# PowerConverter.net
KiCad netlist of a schematic drawn in Altium Designer
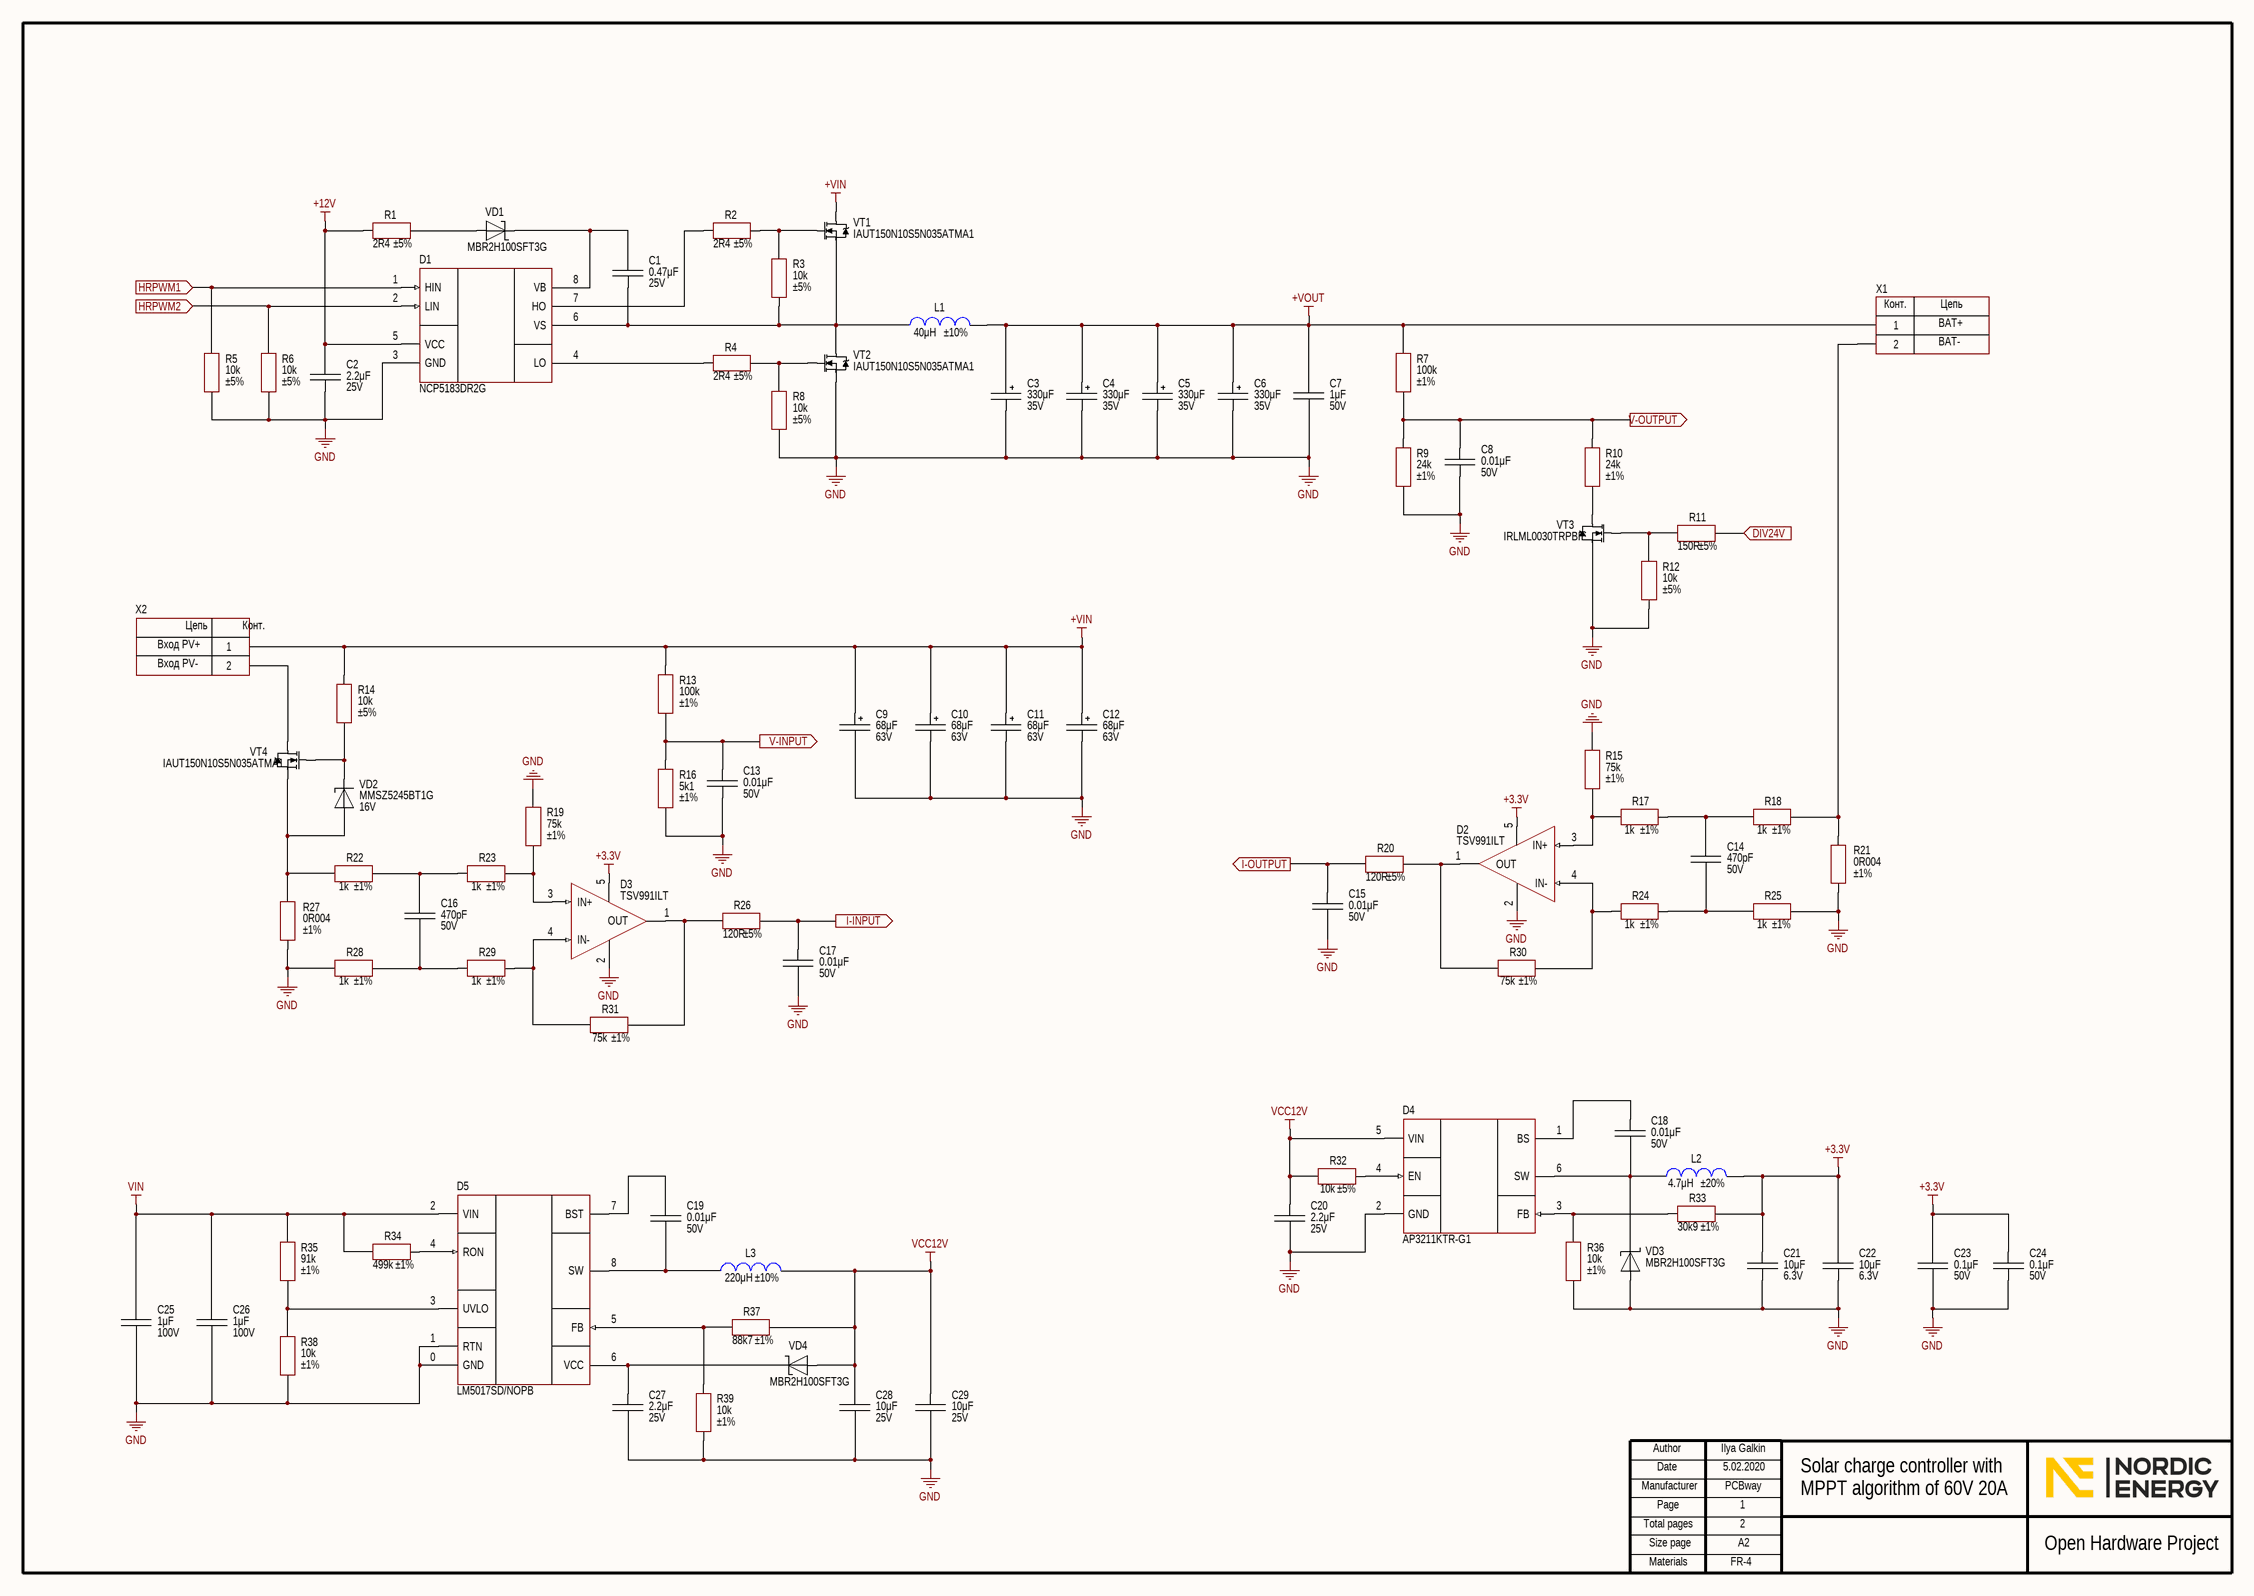
[diagram p0: PowerConverter.SchDoc]

(export (version "E")
  (design (tool "Eeschema 10.0.6"))
  (components
    (comp (ref "C1")
      (value "0.47μF")
      (footprint "CAP: 0805")
      (fields
        (field (name "MANUFACTURER") "Samsung")
        (field (name "PARTNUMBER") "CL21B474KAFNNNG")
        (field (name "VALUEMANUFACTURERPARTNUMBER") "Ceramic capacitor, 0.47μF, X7R, ±10%, 25V, 0805, -55...+125°C")
        (field (name "VOLTAGE") "25V")
      )
      (libsource (lib "Capacitor") (part "Ceramic_0805"))
    )
    (comp (ref "C2")
      (value "2.2μF")
      (footprint "CAP: 0805")
      (fields
        (field (name "MANUFACTURER") "Samsung")
        (field (name "PARTNUMBER") "CL21B225KAFNFNE")
        (field (name "VALUEMANUFACTURERPARTNUMBER") "Ceramic capacitor, 2.2μF, X7R, ±10%, 25V, 0805, -55...+125°C")
        (field (name "VOLTAGE") "25V")
      )
      (libsource (lib "Capacitor") (part "Ceramic_0805"))
    )
    (comp (ref "C3")
      (value "330μF")
      (footprint "CAP: D10C5H12.5")
      (fields
        (field (name "MANUFACTURER") "Panasonic")
        (field (name "PARTNUMBER") "35SEK330M")
        (field (name "VALUEMANUFACTURERPARTNUMBER") "Solid polymer capacitor, 330μF, 35V, ±20%, 18mOhm, 13x10x5 mm, -55...+105°C")
        (field (name "VOLTAGE") "35V")
      )
      (libsource (lib "Capacitor") (part "Aluminium"))
    )
    (comp (ref "C4")
      (value "330μF")
      (footprint "CAP: D10C5H12.5")
      (fields
        (field (name "MANUFACTURER") "Panasonic")
        (field (name "PARTNUMBER") "35SEK330M")
        (field (name "VALUEMANUFACTURERPARTNUMBER") "Solid polymer capacitor, 330μF, 35V, ±20%, 18mOhm, 13x10x5 mm, -55...+105°C")
        (field (name "VOLTAGE") "35V")
      )
      (libsource (lib "Capacitor") (part "Aluminium"))
    )
    (comp (ref "C5")
      (value "330μF")
      (footprint "CAP: D10C5H12.5")
      (fields
        (field (name "MANUFACTURER") "Panasonic")
        (field (name "PARTNUMBER") "35SEK330M")
        (field (name "VALUEMANUFACTURERPARTNUMBER") "Solid polymer capacitor, 330μF, 35V, ±20%, 18mOhm, 13x10x5 mm, -55...+105°C")
        (field (name "VOLTAGE") "35V")
      )
      (libsource (lib "Capacitor") (part "Aluminium"))
    )
    (comp (ref "C6")
      (value "330μF")
      (footprint "CAP: D10C5H12.5")
      (fields
        (field (name "MANUFACTURER") "Panasonic")
        (field (name "PARTNUMBER") "35SEK330M")
        (field (name "VALUEMANUFACTURERPARTNUMBER") "Solid polymer capacitor, 330μF, 35V, ±20%, 18mOhm, 13x10x5 mm, -55...+105°C")
        (field (name "VOLTAGE") "35V")
      )
      (libsource (lib "Capacitor") (part "Aluminium"))
    )
    (comp (ref "C7")
      (value "1μF")
      (footprint "CAP: 0805")
      (fields
        (field (name "MANUFACTURER") "Samsung")
        (field (name "PARTNUMBER") "CL21B105KBFNNNG")
        (field (name "VALUEMANUFACTURERPARTNUMBER") "Ceramic capacitor, 1μF, X7R, ±10%, 50V, 0805, -55...+125°C")
        (field (name "VOLTAGE") "50V")
      )
      (libsource (lib "Capacitor") (part "Ceramic_0805"))
    )
    (comp (ref "C8")
      (value "0.01μF")
      (footprint "CAP: 0805")
      (fields
        (field (name "MANUFACTURER") "Samsung")
        (field (name "PARTNUMBER") "CL21B103KBANNNC")
        (field (name "VALUEMANUFACTURERPARTNUMBER") "Ceramic capacitor, 0.01μF, X7R, ±10%, 50V, 0805, -55...+125°C")
        (field (name "VOLTAGE") "50V")
      )
      (libsource (lib "Capacitor") (part "Ceramic_0805"))
    )
    (comp (ref "C9")
      (value "68μF")
      (footprint "CAP: D10C5H12.5")
      (fields
        (field (name "MANUFACTURER") "Panasonic")
        (field (name "PARTNUMBER") "63SXE68M")
        (field (name "VALUEMANUFACTURERPARTNUMBER") "Solid polymer capacitor, 68μF, 63V, ±20%, 25mOhm, 13x10x5 mm, -55...+105°C")
        (field (name "VOLTAGE") "63V")
      )
      (libsource (lib "Capacitor") (part "Aluminium"))
    )
    (comp (ref "C10")
      (value "68μF")
      (footprint "CAP: D10C5H12.5")
      (fields
        (field (name "MANUFACTURER") "Panasonic")
        (field (name "PARTNUMBER") "63SXE68M")
        (field (name "VALUEMANUFACTURERPARTNUMBER") "Solid polymer capacitor, 68μF, 63V, ±20%, 25mOhm, 13x10x5 mm, -55...+105°C")
        (field (name "VOLTAGE") "63V")
      )
      (libsource (lib "Capacitor") (part "Aluminium"))
    )
    (comp (ref "C11")
      (value "68μF")
      (footprint "CAP: D10C5H12.5")
      (fields
        (field (name "MANUFACTURER") "Panasonic")
        (field (name "PARTNUMBER") "63SXE68M")
        (field (name "VALUEMANUFACTURERPARTNUMBER") "Solid polymer capacitor, 68μF, 63V, ±20%, 25mOhm, 13x10x5 mm, -55...+105°C")
        (field (name "VOLTAGE") "63V")
      )
      (libsource (lib "Capacitor") (part "Aluminium"))
    )
    (comp (ref "C12")
      (value "68μF")
      (footprint "CAP: D10C5H12.5")
      (fields
        (field (name "MANUFACTURER") "Panasonic")
        (field (name "PARTNUMBER") "63SXE68M")
        (field (name "VALUEMANUFACTURERPARTNUMBER") "Solid polymer capacitor, 68μF, 63V, ±20%, 25mOhm, 13x10x5 mm, -55...+105°C")
        (field (name "VOLTAGE") "63V")
      )
      (libsource (lib "Capacitor") (part "Aluminium"))
    )
    (comp (ref "C13")
      (value "0.01μF")
      (footprint "CAP: 0805")
      (fields
        (field (name "MANUFACTURER") "Samsung")
        (field (name "PARTNUMBER") "CL21B103KBANNNC")
        (field (name "VALUEMANUFACTURERPARTNUMBER") "Ceramic capacitor, 0.01μF, X7R, ±10%, 50V, 0805, -55...+125°C")
        (field (name "VOLTAGE") "50V")
      )
      (libsource (lib "Capacitor") (part "Ceramic_0805"))
    )
    (comp (ref "C14")
      (value "470pF")
      (footprint "CAP: 0805")
      (fields
        (field (name "MANUFACTURER") "Samsung")
        (field (name "PARTNUMBER") "CL21B471KBANNNC")
        (field (name "VALUEMANUFACTURERPARTNUMBER") "Ceramic capacitor, 470pF, X7R, ±10%, 50V, 0805, -55...+125°C")
        (field (name "VOLTAGE") "50V")
      )
      (libsource (lib "Capacitor") (part "Ceramic_0805"))
    )
    (comp (ref "C15")
      (value "0.01μF")
      (footprint "CAP: 0805")
      (fields
        (field (name "MANUFACTURER") "Samsung")
        (field (name "PARTNUMBER") "CL21B103KBANNNC")
        (field (name "VALUEMANUFACTURERPARTNUMBER") "Ceramic capacitor, 0.01μF, X7R, ±10%, 50V, 0805, -55...+125°C")
        (field (name "VOLTAGE") "50V")
      )
      (libsource (lib "Capacitor") (part "Ceramic_0805"))
    )
    (comp (ref "C16")
      (value "470pF")
      (footprint "CAP: 0805")
      (fields
        (field (name "MANUFACTURER") "Samsung")
        (field (name "PARTNUMBER") "CL21B471KBANNNC")
        (field (name "VALUEMANUFACTURERPARTNUMBER") "Ceramic capacitor, 470pF, X7R, ±10%, 50V, 0805, -55...+125°C")
        (field (name "VOLTAGE") "50V")
      )
      (libsource (lib "Capacitor") (part "Ceramic_0805"))
    )
    (comp (ref "C17")
      (value "0.01μF")
      (footprint "CAP: 0805")
      (fields
        (field (name "MANUFACTURER") "Samsung")
        (field (name "PARTNUMBER") "CL21B103KBANNNC")
        (field (name "VALUEMANUFACTURERPARTNUMBER") "Ceramic capacitor, 0.01μF, X7R, ±10%, 50V, 0805, -55...+125°C")
        (field (name "VOLTAGE") "50V")
      )
      (libsource (lib "Capacitor") (part "Ceramic_0805"))
    )
    (comp (ref "C18")
      (value "0.01μF")
      (footprint "CAP: 0805")
      (fields
        (field (name "MANUFACTURER") "Samsung")
        (field (name "PARTNUMBER") "CL21B103KBANNNC")
        (field (name "VALUEMANUFACTURERPARTNUMBER") "Ceramic capacitor, 0.01μF, X7R, ±10%, 50V, 0805, -55...+125°C")
        (field (name "VOLTAGE") "50V")
      )
      (libsource (lib "Capacitor") (part "Ceramic_0805"))
    )
    (comp (ref "C19")
      (value "0.01μF")
      (footprint "CAP: 0805")
      (fields
        (field (name "MANUFACTURER") "Samsung")
        (field (name "PARTNUMBER") "CL21B103KBANNNC")
        (field (name "VALUEMANUFACTURERPARTNUMBER") "Ceramic capacitor, 0.01μF, X7R, ±10%, 50V, 0805, -55...+125°C")
        (field (name "VOLTAGE") "50V")
      )
      (libsource (lib "Capacitor") (part "Ceramic_0805"))
    )
    (comp (ref "C20")
      (value "2.2μF")
      (footprint "CAP: 0805")
      (fields
        (field (name "MANUFACTURER") "Samsung")
        (field (name "PARTNUMBER") "CL21B225KAFNFNE")
        (field (name "VALUEMANUFACTURERPARTNUMBER") "Ceramic capacitor, 2.2μF, X7R, ±10%, 25V, 0805, -55...+125°C")
        (field (name "VOLTAGE") "25V")
      )
      (libsource (lib "Capacitor") (part "Ceramic_0805"))
    )
    (comp (ref "C21")
      (value "10μF")
      (footprint "CAP: 0805")
      (fields
        (field (name "MANUFACTURER") "Samsung")
        (field (name "PARTNUMBER") "CL21B106KQQNNNG")
        (field (name "VALUEMANUFACTURERPARTNUMBER") "Ceramic capacitor, 10μF, X7R, ±10%, 6.3V, 0805, -55...+125°C")
        (field (name "VOLTAGE") "6.3V")
      )
      (libsource (lib "Capacitor") (part "Ceramic_0805"))
    )
    (comp (ref "C22")
      (value "10μF")
      (footprint "CAP: 0805")
      (fields
        (field (name "MANUFACTURER") "Samsung")
        (field (name "PARTNUMBER") "CL21B106KQQNNNG")
        (field (name "VALUEMANUFACTURERPARTNUMBER") "Ceramic capacitor, 10μF, X7R, ±10%, 6.3V, 0805, -55...+125°C")
        (field (name "VOLTAGE") "6.3V")
      )
      (libsource (lib "Capacitor") (part "Ceramic_0805"))
    )
    (comp (ref "C23")
      (value "0.1μF")
      (footprint "CAP: 0805")
      (fields
        (field (name "MANUFACTURER") "Samsung")
        (field (name "PARTNUMBER") "CL21B104KBCNFNC")
        (field (name "VALUEMANUFACTURERPARTNUMBER") "Ceramic capacitor, 0.1μF, X7R, ±10%, 50V, 0805, -55...+125°C")
        (field (name "VOLTAGE") "50V")
      )
      (libsource (lib "Capacitor") (part "Ceramic_0805"))
    )
    (comp (ref "C24")
      (value "0.1μF")
      (footprint "CAP: 0805")
      (fields
        (field (name "MANUFACTURER") "Samsung")
        (field (name "PARTNUMBER") "CL21B104KBCNFNC")
        (field (name "VALUEMANUFACTURERPARTNUMBER") "Ceramic capacitor, 0.1μF, X7R, ±10%, 50V, 0805, -55...+125°C")
        (field (name "VOLTAGE") "50V")
      )
      (libsource (lib "Capacitor") (part "Ceramic_0805"))
    )
    (comp (ref "C25")
      (value "1μF")
      (footprint "CAP: 1206")
      (fields
        (field (name "MANUFACTURER") "Samsung")
        (field (name "PARTNUMBER") "CL31B105KCHSNNE")
        (field (name "VALUEMANUFACTURERPARTNUMBER") "Ceramic capacitor, 1μF, X7R, ±10%, 100V, 1206, -55...+125°C")
        (field (name "VOLTAGE") "100V")
      )
      (libsource (lib "Capacitor") (part "Ceramic_1206"))
    )
    (comp (ref "C26")
      (value "1μF")
      (footprint "CAP: 1206")
      (fields
        (field (name "MANUFACTURER") "Samsung")
        (field (name "PARTNUMBER") "CL31B105KCHSNNE")
        (field (name "VALUEMANUFACTURERPARTNUMBER") "Ceramic capacitor, 1μF, X7R, ±10%, 100V, 1206, -55...+125°C")
        (field (name "VOLTAGE") "100V")
      )
      (libsource (lib "Capacitor") (part "Ceramic_1206"))
    )
    (comp (ref "C27")
      (value "2.2μF")
      (footprint "CAP: 0805")
      (fields
        (field (name "MANUFACTURER") "Samsung")
        (field (name "PARTNUMBER") "CL21B225KAFNFNE")
        (field (name "VALUEMANUFACTURERPARTNUMBER") "Ceramic capacitor, 2.2μF, X7R, ±10%, 25V, 0805, -55...+125°C")
        (field (name "VOLTAGE") "25V")
      )
      (libsource (lib "Capacitor") (part "Ceramic_0805"))
    )
    (comp (ref "C28")
      (value "10μF")
      (footprint "CAP: 1206")
      (fields
        (field (name "MANUFACTURER") "Samsung")
        (field (name "PARTNUMBER") "CL31B106KAHNNNE")
        (field (name "VALUEMANUFACTURERPARTNUMBER") "Ceramic capacitor, 10μF, X7R, ±10%, 25V, 1206, -55...+125°C")
        (field (name "VOLTAGE") "25V")
      )
      (libsource (lib "Capacitor") (part "Ceramic_1206"))
    )
    (comp (ref "C29")
      (value "10μF")
      (footprint "CAP: 1206")
      (fields
        (field (name "MANUFACTURER") "Samsung")
        (field (name "PARTNUMBER") "CL31B106KAHNNNE")
        (field (name "VALUEMANUFACTURERPARTNUMBER") "Ceramic capacitor, 10μF, X7R, ±10%, 25V, 1206, -55...+125°C")
        (field (name "VOLTAGE") "25V")
      )
      (libsource (lib "Capacitor") (part "Ceramic_1206"))
    )
    (comp (ref "D1")
      (value "~")
      (footprint "8-SOIC")
      (description "Gate driver")
      (fields
        (field (name "MANUFACTURER") "ON Semiconductor")
        (field (name "VALUEMANUFACTURERPARTNUMBER") "Half-bridge gate driver, 600V, 500kHz, ±4.3A, supply 9...18V, -40...+125°C, 8-SOIC")
        (field (name "PARTNUMBER") "NCP5183DR2G")
      )
      (libsource (lib "IC. Gate driver") (part "NCP5183DR2G"))
    )
    (comp (ref "D2")
      (value "~")
      (footprint "SOT23-5")
      (description "OP amplifier")
      (fields
        (field (name "MANUFACTURER") "STMicroelectronics")
        (field (name "VALUEMANUFACTURERPARTNUMBER") "IC op amplifier, Rail-to-Rail, 20 MHz, 2.7...5.5V, -40...+125°C, SOT23-5")
        (field (name "PARTNUMBER") "TSV991ILT")
      )
      (libsource (lib "IC. Amplifier") (part "TSV991ILT"))
    )
    (comp (ref "D3")
      (value "~")
      (footprint "SOT23-5")
      (description "OP amplifier")
      (fields
        (field (name "MANUFACTURER") "STMicroelectronics")
        (field (name "VALUEMANUFACTURERPARTNUMBER") "IC op amplifier, Rail-to-Rail, 20 MHz, 2.7...5.5V, -40...+125°C, SOT23-5")
        (field (name "PARTNUMBER") "TSV991ILT")
      )
      (libsource (lib "IC. Amplifier") (part "TSV991ILT"))
    )
    (comp (ref "D4")
      (value "~")
      (footprint "SOT23-6")
      (description "Buck converter")
      (fields
        (field (name "MANUFACTURER") "Diodes Incorporated")
        (field (name "VALUEMANUFACTURERPARTNUMBER") "DC/DC buck converter, input 4.5...18V, 1.4MHz, output 0.81...15V, 1.5A, -40...+85°C, SOT23-6")
        (field (name "PARTNUMBER") "AP3211KTR-G1")
      )
      (libsource (lib "IC. Power supply") (part "AP3211KTR-G1"))
    )
    (comp (ref "D5")
      (value "~")
      (footprint "8-WSON (4x4)")
      (description "Buck converter")
      (fields
        (field (name "MANUFACTURER") "Texas Instruments")
        (field (name "VALUEMANUFACTURERPARTNUMBER") "DC/DC buck converter, input 7.5...100V, 1MHz, output 1.225...90V, 0.6A, -40...+125°C, 8-WSON")
        (field (name "PARTNUMBER") "LM5017SD/NOPB")
      )
      (libsource (lib "IC. Power supply") (part "LM5017SD"))
    )
    (comp (ref "L1")
      (value "40μH")
      (footprint "IND: R32.8/20.1/10.7 (L)")
      (fields
        (field (name "MANUFACTURER") "Magnetics")
        (field (name "PARTNUMBER") "0077548A7")
        (field (name "VALUEMANUFACTURERPARTNUMBER") "Fixed inductor, 40μH, ±10%, R32.8/20.1/10.7, Kool Mu, µ=125, 127 нГн/витков2")
        (field (name "TOLERANCE") "±10%")
      )
      (libsource (lib "Inductor") (part "Inductor_R32.8/20.1/10.7"))
    )
    (comp (ref "L2")
      (value "4.7μH")
      (footprint "IND: SDR0403")
      (fields
        (field (name "MANUFACTURER") "Bourns")
        (field (name "PARTNUMBER") "SDR0403-4R7ML")
        (field (name "VALUEMANUFACTURERPARTNUMBER") "Fixed inductor, 4.7μH, ±20%, SDR0403, 1.7A, -40...+125°C")
        (field (name "TOLERANCE") "±20%")
      )
      (libsource (lib "Inductor") (part "Inductor_SDR0403"))
    )
    (comp (ref "L3")
      (value "220μH")
      (footprint "IND: SDR0805")
      (fields
        (field (name "MANUFACTURER") "Bourns")
        (field (name "PARTNUMBER") "SDR0805-221KL")
        (field (name "VALUEMANUFACTURERPARTNUMBER") "Fixed inductor, 220μH, ±10%, SDR0805, 490mA, -40...+125°C")
        (field (name "TOLERANCE") "±10%")
      )
      (libsource (lib "Inductor") (part "Inductor_SDR0805"))
    )
    (comp (ref "R1")
      (value "2R4")
      (footprint "RES: 0805")
      (fields
        (field (name "MANUFACTURER") "Yageo")
        (field (name "PARTNUMBER") "RC0805JR-072R4L")
        (field (name "VALUEMANUFACTURERPARTNUMBER") "Resistor film, 2R4, ±5%, 0805, 0.125W, -55...+125°C")
        (field (name "TOLERANCE") "±5%")
      )
      (libsource (lib "Resistor") (part "Resistor_0805"))
    )
    (comp (ref "R2")
      (value "2R4")
      (footprint "RES: 0805")
      (fields
        (field (name "MANUFACTURER") "Yageo")
        (field (name "PARTNUMBER") "RC0805JR-072R4L")
        (field (name "VALUEMANUFACTURERPARTNUMBER") "Resistor film, 2R4, ±5%, 0805, 0.125W, -55...+125°C")
        (field (name "TOLERANCE") "±5%")
      )
      (libsource (lib "Resistor") (part "Resistor_0805"))
    )
    (comp (ref "R3")
      (value "10k")
      (footprint "RES: 0805")
      (fields
        (field (name "MANUFACTURER") "Yageo")
        (field (name "PARTNUMBER") "RC0805JR-0710KL")
        (field (name "VALUEMANUFACTURERPARTNUMBER") "Resistor film, 10k, ±5%, 0805, 0.125W, -55...+125°C")
        (field (name "TOLERANCE") "±5%")
      )
      (libsource (lib "") (part "Resistor_0805_1"))
    )
    (comp (ref "R4")
      (value "2R4")
      (footprint "RES: 0805")
      (fields
        (field (name "MANUFACTURER") "Yageo")
        (field (name "PARTNUMBER") "RC0805JR-072R4L")
        (field (name "VALUEMANUFACTURERPARTNUMBER") "Resistor film, 2R4, ±5%, 0805, 0.125W, -55...+125°C")
        (field (name "TOLERANCE") "±5%")
      )
      (libsource (lib "Resistor") (part "Resistor_0805"))
    )
    (comp (ref "R5")
      (value "10k")
      (footprint "RES: 0805")
      (fields
        (field (name "MANUFACTURER") "Yageo")
        (field (name "PARTNUMBER") "RC0805JR-0710KL")
        (field (name "VALUEMANUFACTURERPARTNUMBER") "Resistor film, 10k, ±5%, 0805, 0.125W, -55...+125°C")
        (field (name "TOLERANCE") "±5%")
      )
      (libsource (lib "") (part "Resistor_0805_1"))
    )
    (comp (ref "R6")
      (value "10k")
      (footprint "RES: 0805")
      (fields
        (field (name "MANUFACTURER") "Yageo")
        (field (name "PARTNUMBER") "RC0805JR-0710KL")
        (field (name "VALUEMANUFACTURERPARTNUMBER") "Resistor film, 10k, ±5%, 0805, 0.125W, -55...+125°C")
        (field (name "TOLERANCE") "±5%")
      )
      (libsource (lib "") (part "Resistor_0805_1"))
    )
    (comp (ref "R7")
      (value "100k")
      (footprint "RES: 0805")
      (fields
        (field (name "MANUFACTURER") "Yageo")
        (field (name "PARTNUMBER") "RC0805FR-07100KL")
        (field (name "VALUEMANUFACTURERPARTNUMBER") "Resistor film, 100k, ±1%, 0805, 0.125W, -55...+125°C")
        (field (name "TOLERANCE") "±1%")
      )
      (libsource (lib "") (part "Resistor_0805_1"))
    )
    (comp (ref "R8")
      (value "10k")
      (footprint "RES: 0805")
      (fields
        (field (name "MANUFACTURER") "Yageo")
        (field (name "PARTNUMBER") "RC0805JR-0710KL")
        (field (name "VALUEMANUFACTURERPARTNUMBER") "Resistor film, 10k, ±5%, 0805, 0.125W, -55...+125°C")
        (field (name "TOLERANCE") "±5%")
      )
      (libsource (lib "") (part "Resistor_0805_1"))
    )
    (comp (ref "R9")
      (value "24k")
      (footprint "RES: 0805")
      (fields
        (field (name "MANUFACTURER") "Yageo")
        (field (name "PARTNUMBER") "RC0805FR-0724KL")
        (field (name "VALUEMANUFACTURERPARTNUMBER") "Resistor film, 24k, ±1%, 0805, 0.125W, -55...+125°C")
        (field (name "TOLERANCE") "±1%")
      )
      (libsource (lib "") (part "Resistor_0805_1"))
    )
    (comp (ref "R10")
      (value "24k")
      (footprint "RES: 0805")
      (fields
        (field (name "MANUFACTURER") "Yageo")
        (field (name "PARTNUMBER") "RC0805FR-0724KL")
        (field (name "VALUEMANUFACTURERPARTNUMBER") "Resistor film, 24k, ±1%, 0805, 0.125W, -55...+125°C")
        (field (name "TOLERANCE") "±1%")
      )
      (libsource (lib "") (part "Resistor_0805_1"))
    )
    (comp (ref "R11")
      (value "150R")
      (footprint "RES: 0805")
      (fields
        (field (name "MANUFACTURER") "Yageo")
        (field (name "PARTNUMBER") "RC0805JR-07150RL")
        (field (name "VALUEMANUFACTURERPARTNUMBER") "Resistor film, 150R, ±5%, 0805, 0.125W, -55...+125°C")
        (field (name "TOLERANCE") "±5%")
      )
      (libsource (lib "Resistor") (part "Resistor_0805"))
    )
    (comp (ref "R12")
      (value "10k")
      (footprint "RES: 0805")
      (fields
        (field (name "MANUFACTURER") "Yageo")
        (field (name "PARTNUMBER") "RC0805JR-0710KL")
        (field (name "VALUEMANUFACTURERPARTNUMBER") "Resistor film, 10k, ±5%, 0805, 0.125W, -55...+125°C")
        (field (name "TOLERANCE") "±5%")
      )
      (libsource (lib "") (part "Resistor_0805_1"))
    )
    (comp (ref "R13")
      (value "100k")
      (footprint "RES: 0805")
      (fields
        (field (name "MANUFACTURER") "Yageo")
        (field (name "PARTNUMBER") "RC0805FR-07100KL")
        (field (name "VALUEMANUFACTURERPARTNUMBER") "Resistor film, 100k, ±1%, 0805, 0.125W, -55...+125°C")
        (field (name "TOLERANCE") "±1%")
      )
      (libsource (lib "") (part "Resistor_0805_1"))
    )
    (comp (ref "R14")
      (value "10k")
      (footprint "RES: 0805")
      (fields
        (field (name "MANUFACTURER") "Yageo")
        (field (name "PARTNUMBER") "RC0805JR-0710KL")
        (field (name "VALUEMANUFACTURERPARTNUMBER") "Resistor film, 10k, ±5%, 0805, 0.125W, -55...+125°C")
        (field (name "TOLERANCE") "±5%")
      )
      (libsource (lib "") (part "Resistor_0805_1"))
    )
    (comp (ref "R15")
      (value "75k")
      (footprint "RES: 0805")
      (fields
        (field (name "MANUFACTURER") "Yageo")
        (field (name "PARTNUMBER") "RC0805FR-0775KL")
        (field (name "VALUEMANUFACTURERPARTNUMBER") "Resistor film, 75k, ±1%, 0805, 0.125W, -55...+125°C")
        (field (name "TOLERANCE") "±1%")
      )
      (libsource (lib "") (part "Resistor_0805_1"))
    )
    (comp (ref "R16")
      (value "5k1")
      (footprint "RES: 0805")
      (fields
        (field (name "MANUFACTURER") "Yageo")
        (field (name "PARTNUMBER") "RC0805FR-075K1L")
        (field (name "VALUEMANUFACTURERPARTNUMBER") "Resistor film, 5k1, ±1%, 0805, 0.125W, -55...+125°C")
        (field (name "TOLERANCE") "±1%")
      )
      (libsource (lib "") (part "Resistor_0805_1"))
    )
    (comp (ref "R17")
      (value "1k")
      (footprint "RES: 0805")
      (fields
        (field (name "MANUFACTURER") "Yageo")
        (field (name "PARTNUMBER") "RC0805FR-071KL")
        (field (name "VALUEMANUFACTURERPARTNUMBER") "Resistor film, 1k, ±1%, 0805, 0.125W, -55...+125°C")
        (field (name "TOLERANCE") "±1%")
      )
      (libsource (lib "Resistor") (part "Resistor_0805"))
    )
    (comp (ref "R18")
      (value "1k")
      (footprint "RES: 0805")
      (fields
        (field (name "MANUFACTURER") "Yageo")
        (field (name "PARTNUMBER") "RC0805FR-071KL")
        (field (name "VALUEMANUFACTURERPARTNUMBER") "Resistor film, 1k, ±1%, 0805, 0.125W, -55...+125°C")
        (field (name "TOLERANCE") "±1%")
      )
      (libsource (lib "Resistor") (part "Resistor_0805"))
    )
    (comp (ref "R19")
      (value "75k")
      (footprint "RES: 0805")
      (fields
        (field (name "MANUFACTURER") "Yageo")
        (field (name "PARTNUMBER") "RC0805FR-0775KL")
        (field (name "VALUEMANUFACTURERPARTNUMBER") "Resistor film, 75k, ±1%, 0805, 0.125W, -55...+125°C")
        (field (name "TOLERANCE") "±1%")
      )
      (libsource (lib "") (part "Resistor_0805_1"))
    )
    (comp (ref "R20")
      (value "120R")
      (footprint "RES: 0805")
      (fields
        (field (name "MANUFACTURER") "Yageo")
        (field (name "PARTNUMBER") "RC0805JR-07120RL")
        (field (name "VALUEMANUFACTURERPARTNUMBER") "Resistor film, 120R, ±5%, 0805, 0.125W, -55...+125°C")
        (field (name "TOLERANCE") "±5%")
      )
      (libsource (lib "Resistor") (part "Resistor_0805"))
    )
    (comp (ref "R21")
      (value "0R004")
      (footprint "RES: CSS2H (2512)")
      (fields
        (field (name "MANUFACTURER") "Bourns")
        (field (name "PARTNUMBER") "CRE2512-FZ-R004E-3")
        (field (name "VALUEMANUFACTURERPARTNUMBER") "Resistor film, 0R004, ±1%, 2512, 5W, -55...+170°C")
        (field (name "TOLERANCE") "±1%")
      )
      (libsource (lib "Resistor") (part "Shunt"))
    )
    (comp (ref "R22")
      (value "1k")
      (footprint "RES: 0805")
      (fields
        (field (name "MANUFACTURER") "Yageo")
        (field (name "PARTNUMBER") "RC0805FR-071KL")
        (field (name "VALUEMANUFACTURERPARTNUMBER") "Resistor film, 1k, ±1%, 0805, 0.125W, -55...+125°C")
        (field (name "TOLERANCE") "±1%")
      )
      (libsource (lib "Resistor") (part "Resistor_0805"))
    )
    (comp (ref "R23")
      (value "1k")
      (footprint "RES: 0805")
      (fields
        (field (name "MANUFACTURER") "Yageo")
        (field (name "PARTNUMBER") "RC0805FR-071KL")
        (field (name "VALUEMANUFACTURERPARTNUMBER") "Resistor film, 1k, ±1%, 0805, 0.125W, -55...+125°C")
        (field (name "TOLERANCE") "±1%")
      )
      (libsource (lib "Resistor") (part "Resistor_0805"))
    )
    (comp (ref "R24")
      (value "1k")
      (footprint "RES: 0805")
      (fields
        (field (name "MANUFACTURER") "Yageo")
        (field (name "PARTNUMBER") "RC0805FR-071KL")
        (field (name "VALUEMANUFACTURERPARTNUMBER") "Resistor film, 1k, ±1%, 0805, 0.125W, -55...+125°C")
        (field (name "TOLERANCE") "±1%")
      )
      (libsource (lib "Resistor") (part "Resistor_0805"))
    )
    (comp (ref "R25")
      (value "1k")
      (footprint "RES: 0805")
      (fields
        (field (name "MANUFACTURER") "Yageo")
        (field (name "PARTNUMBER") "RC0805FR-071KL")
        (field (name "VALUEMANUFACTURERPARTNUMBER") "Resistor film, 1k, ±1%, 0805, 0.125W, -55...+125°C")
        (field (name "TOLERANCE") "±1%")
      )
      (libsource (lib "Resistor") (part "Resistor_0805"))
    )
    (comp (ref "R26")
      (value "120R")
      (footprint "RES: 0805")
      (fields
        (field (name "MANUFACTURER") "Yageo")
        (field (name "PARTNUMBER") "RC0805JR-07120RL")
        (field (name "VALUEMANUFACTURERPARTNUMBER") "Resistor film, 120R, ±5%, 0805, 0.125W, -55...+125°C")
        (field (name "TOLERANCE") "±5%")
      )
      (libsource (lib "Resistor") (part "Resistor_0805"))
    )
    (comp (ref "R27")
      (value "0R004")
      (footprint "RES: CSS2H (2512)")
      (fields
        (field (name "MANUFACTURER") "Bourns")
        (field (name "PARTNUMBER") "CRE2512-FZ-R004E-3")
        (field (name "VALUEMANUFACTURERPARTNUMBER") "Resistor film, 0R004, ±1%, 2512, 5W, -55...+170°C")
        (field (name "TOLERANCE") "±1%")
      )
      (libsource (lib "Resistor") (part "Shunt"))
    )
    (comp (ref "R28")
      (value "1k")
      (footprint "RES: 0805")
      (fields
        (field (name "MANUFACTURER") "Yageo")
        (field (name "PARTNUMBER") "RC0805FR-071KL")
        (field (name "VALUEMANUFACTURERPARTNUMBER") "Resistor film, 1k, ±1%, 0805, 0.125W, -55...+125°C")
        (field (name "TOLERANCE") "±1%")
      )
      (libsource (lib "Resistor") (part "Resistor_0805"))
    )
    (comp (ref "R29")
      (value "1k")
      (footprint "RES: 0805")
      (fields
        (field (name "MANUFACTURER") "Yageo")
        (field (name "PARTNUMBER") "RC0805FR-071KL")
        (field (name "VALUEMANUFACTURERPARTNUMBER") "Resistor film, 1k, ±1%, 0805, 0.125W, -55...+125°C")
        (field (name "TOLERANCE") "±1%")
      )
      (libsource (lib "Resistor") (part "Resistor_0805"))
    )
    (comp (ref "R30")
      (value "75k")
      (footprint "RES: 0805")
      (fields
        (field (name "MANUFACTURER") "Yageo")
        (field (name "PARTNUMBER") "RC0805FR-0775KL")
        (field (name "VALUEMANUFACTURERPARTNUMBER") "Resistor film, 75k, ±1%, 0805, 0.125W, -55...+125°C")
        (field (name "TOLERANCE") "±1%")
      )
      (libsource (lib "Resistor") (part "Resistor_0805"))
    )
    (comp (ref "R31")
      (value "75k")
      (footprint "RES: 0805")
      (fields
        (field (name "MANUFACTURER") "Yageo")
        (field (name "PARTNUMBER") "RC0805FR-0775KL")
        (field (name "VALUEMANUFACTURERPARTNUMBER") "Resistor film, 75k, ±1%, 0805, 0.125W, -55...+125°C")
        (field (name "TOLERANCE") "±1%")
      )
      (libsource (lib "Resistor") (part "Resistor_0805"))
    )
    (comp (ref "R32")
      (value "10k")
      (footprint "RES: 0805")
      (fields
        (field (name "MANUFACTURER") "Yageo")
        (field (name "PARTNUMBER") "RC0805JR-0710KL")
        (field (name "VALUEMANUFACTURERPARTNUMBER") "Resistor film, 10k, ±5%, 0805, 0.125W, -55...+125°C")
        (field (name "TOLERANCE") "±5%")
      )
      (libsource (lib "Resistor") (part "Resistor_0805"))
    )
    (comp (ref "R33")
      (value "30k9")
      (footprint "RES: 0805")
      (fields
        (field (name "MANUFACTURER") "Yageo")
        (field (name "PARTNUMBER") "RC0805FR-0730K9L")
        (field (name "VALUEMANUFACTURERPARTNUMBER") "Resistor film, 30k9, ±1%, 0805, 0.125W, -55...+125°C")
        (field (name "TOLERANCE") "±1%")
      )
      (libsource (lib "Resistor") (part "Resistor_0805"))
    )
    (comp (ref "R34")
      (value "499k")
      (footprint "RES: 0805")
      (fields
        (field (name "MANUFACTURER") "Yageo")
        (field (name "PARTNUMBER") "RC0805FR-07499KL")
        (field (name "VALUEMANUFACTURERPARTNUMBER") "Resistor film, 499k, ±1%, 0805, 0.125W, -55...+125°C")
        (field (name "TOLERANCE") "±1%")
      )
      (libsource (lib "Resistor") (part "Resistor_0805"))
    )
    (comp (ref "R35")
      (value "91k")
      (footprint "RES: 0805")
      (fields
        (field (name "MANUFACTURER") "Yageo")
        (field (name "PARTNUMBER") "RC0805FR-0791KL")
        (field (name "VALUEMANUFACTURERPARTNUMBER") "Resistor film, 91k, ±1%, 0805, 0.125W, -55...+125°C")
        (field (name "TOLERANCE") "±1%")
      )
      (libsource (lib "") (part "Resistor_0805_1"))
    )
    (comp (ref "R36")
      (value "10k")
      (footprint "RES: 0805")
      (fields
        (field (name "MANUFACTURER") "Yageo")
        (field (name "PARTNUMBER") "RC0805FR-0710KL")
        (field (name "VALUEMANUFACTURERPARTNUMBER") "Resistor film, 10k, ±1%, 0805, 0.125W, -55...+125°C")
        (field (name "TOLERANCE") "±1%")
      )
      (libsource (lib "") (part "Resistor_0805_1"))
    )
    (comp (ref "R37")
      (value "88k7")
      (footprint "RES: 0805")
      (fields
        (field (name "MANUFACTURER") "Yageo")
        (field (name "PARTNUMBER") "RC0805FR-0788K7L")
        (field (name "VALUEMANUFACTURERPARTNUMBER") "Resistor film, 88k7, ±1%, 0805, 0.125W, -55...+125°C")
        (field (name "TOLERANCE") "±1%")
      )
      (libsource (lib "Resistor") (part "Resistor_0805"))
    )
    (comp (ref "R38")
      (value "10k")
      (footprint "RES: 0805")
      (fields
        (field (name "MANUFACTURER") "Yageo")
        (field (name "PARTNUMBER") "RC0805FR-0710KL")
        (field (name "VALUEMANUFACTURERPARTNUMBER") "Resistor film, 10k, ±1%, 0805, 0.125W, -55...+125°C")
        (field (name "TOLERANCE") "±1%")
      )
      (libsource (lib "") (part "Resistor_0805_1"))
    )
    (comp (ref "R39")
      (value "10k")
      (footprint "RES: 0805")
      (fields
        (field (name "MANUFACTURER") "Yageo")
        (field (name "PARTNUMBER") "RC0805FR-0710KL")
        (field (name "VALUEMANUFACTURERPARTNUMBER") "Resistor film, 10k, ±1%, 0805, 0.125W, -55...+125°C")
        (field (name "TOLERANCE") "±1%")
      )
      (libsource (lib "") (part "Resistor_0805_1"))
    )
    (comp (ref "VD1")
      (value "~")
      (footprint "DIODE: SOD123F")
      (fields
        (field (name "MANUFACTURER") "ON Semiconductor")
        (field (name "VALUEMANUFACTURERPARTNUMBER") "Schottky diode, 100V, 2A, 840mV, 15pF, SOD-123F, -55...+150°C")
        (field (name "VOLTAGE") "100V")
        (field (name "PARTNUMBER") "MBR2H100SFT3G")
      )
      (libsource (lib "Diode") (part "Schottky_single"))
    )
    (comp (ref "VD2")
      (value "~")
      (footprint "DIODE: SOD123")
      (fields
        (field (name "MANUFACTURER") "ON Semiconductor")
        (field (name "VALUEMANUFACTURERPARTNUMBER") "Zener diode, 16V, 500mW, 0.9V, 16Ohm, SOD-123, -55...+150°C")
        (field (name "VOLTAGE") "16V")
        (field (name "PARTNUMBER") "MMSZ5245BT1G")
      )
      (libsource (lib "Diode") (part "Zener_single"))
    )
    (comp (ref "VD3")
      (value "~")
      (footprint "DIODE: SOD123F")
      (fields
        (field (name "MANUFACTURER") "ON Semiconductor")
        (field (name "VALUEMANUFACTURERPARTNUMBER") "Schottky diode, 100V, 2A, 840mV, 15pF, SOD-123F, -55...+150°C")
        (field (name "VOLTAGE") "100V")
        (field (name "PARTNUMBER") "MBR2H100SFT3G")
      )
      (libsource (lib "Diode") (part "Schottky_single"))
    )
    (comp (ref "VD4")
      (value "~")
      (footprint "DIODE: SOD123F")
      (fields
        (field (name "MANUFACTURER") "ON Semiconductor")
        (field (name "VALUEMANUFACTURERPARTNUMBER") "Schottky diode, 100V, 2A, 840mV, 15pF, SOD-123F, -55...+150°C")
        (field (name "VOLTAGE") "100V")
        (field (name "PARTNUMBER") "MBR2H100SFT3G")
      )
      (libsource (lib "Diode") (part "Schottky_single"))
    )
    (comp (ref "VT1")
      (value "~")
      (footprint "HSOF-8-1")
      (fields
        (field (name "MANUFACTURER") "Infineon Technologies")
        (field (name "VALUEMANUFACTURERPARTNUMBER") "MOSFET N-channel transistor, 100V, 150A, 87nC, 166W, 3.5mOhm, 6110pF, 8-HSOF, -55...+175°C")
        (field (name "PARTNUMBER") "IAUT150N10S5N035ATMA1")
      )
      (libsource (lib "Transistor") (part "MOSFET_N_123"))
    )
    (comp (ref "VT2")
      (value "~")
      (footprint "HSOF-8-1")
      (fields
        (field (name "MANUFACTURER") "Infineon Technologies")
        (field (name "VALUEMANUFACTURERPARTNUMBER") "MOSFET N-channel transistor, 100V, 150A, 87nC, 166W, 3.5mOhm, 6110pF, 8-HSOF, -55...+175°C")
        (field (name "PARTNUMBER") "IAUT150N10S5N035ATMA1")
      )
      (libsource (lib "Transistor") (part "MOSFET_N_123"))
    )
    (comp (ref "VT3")
      (value "~")
      (footprint "SOT23")
      (fields
        (field (name "MANUFACTURER") "Infineon Technologies")
        (field (name "VALUEMANUFACTURERPARTNUMBER") "MOSFET N-channel transistor, 30V, 5.3A, 2.6nC, 1.3W, 27mOhm, 382pF, SOT-23, -55...+150°C")
        (field (name "PARTNUMBER") "IRLML0030TRPBF")
      )
      (libsource (lib "Transistor") (part "MOSFET_N_132"))
    )
    (comp (ref "VT4")
      (value "~")
      (footprint "HSOF-8-1")
      (fields
        (field (name "MANUFACTURER") "Infineon Technologies")
        (field (name "VALUEMANUFACTURERPARTNUMBER") "MOSFET N-channel transistor, 100V, 150A, 87nC, 166W, 3.5mOhm, 6110pF, 8-HSOF, -55...+175°C")
        (field (name "PARTNUMBER") "IAUT150N10S5N035ATMA1")
      )
      (libsource (lib "Transistor") (part "MOSFET_N_123"))
    )
    (comp (ref "X1")
      (value "~")
      (footprint "CON: XT60PW-M")
      (fields
        (field (name "MANUFACTURER") "AMASS")
        (field (name "VALUEMANUFACTURERPARTNUMBER") "Power connector, 2pin, 7.2mm, 500V, 60A")
        (field (name "PARTNUMBER") "XT60PW-M")
      )
      (libsource (lib "") (part "Connector_XT_2pin_1"))
    )
    (comp (ref "X2")
      (value "~")
      (footprint "CON: XT60PW-M")
      (fields
        (field (name "MANUFACTURER") "AMASS")
        (field (name "VALUEMANUFACTURERPARTNUMBER") "Power connector, 2pin, 7.2mm, 500V, 60A")
        (field (name "PARTNUMBER") "XT60PW-M")
      )
      (libsource (lib "Connector") (part "Connector_XT_2pin"))
    )
  )
  (nets
    (net (code "1") (name "+3.3V") (class "Default")
      (node (ref "C21") (pin "2") (pinfunction "2_2") (pintype "power_in"))
      (node (ref "C22") (pin "2") (pinfunction "2_2") (pintype "power_in"))
      (node (ref "C23") (pin "2") (pinfunction "2_2") (pintype "power_in"))
      (node (ref "C24") (pin "2") (pinfunction "2_2") (pintype "power_in"))
      (node (ref "D2") (pin "5") (pinfunction "V+_5") (pintype "power_in"))
      (node (ref "D3") (pin "5") (pinfunction "V+_5") (pintype "power_in"))
      (node (ref "L2") (pin "1") (pinfunction "1_1") (pintype "passive"))
      (node (ref "R33") (pin "1") (pinfunction "1_1") (pintype "passive"))
    )
    (net (code "2") (name "+12V") (class "Default")
      (node (ref "C2") (pin "2") (pinfunction "2_2") (pintype "power_in"))
      (node (ref "D1") (pin "5") (pinfunction "VCC_5") (pintype "passive"))
      (node (ref "R1") (pin "2") (pinfunction "2_2") (pintype "passive"))
    )
    (net (code "3") (name "+VIN") (class "Default")
      (node (ref "C10") (pin "1") (pinfunction "1_1") (pintype "power_in"))
      (node (ref "C11") (pin "1") (pinfunction "1_1") (pintype "power_in"))
      (node (ref "C12") (pin "1") (pinfunction "1_1") (pintype "power_in"))
      (node (ref "C9") (pin "1") (pinfunction "1_1") (pintype "power_in"))
      (node (ref "R13") (pin "2") (pinfunction "2_2") (pintype "passive"))
      (node (ref "R14") (pin "2") (pinfunction "2_2") (pintype "passive"))
      (node (ref "VT1") (pin "2") (pinfunction "D_2") (pintype "passive"))
      (node (ref "X2") (pin "1") (pinfunction "1_1") (pintype "passive"))
    )
    (net (code "4") (name "+VOUT") (class "Default")
      (node (ref "C3") (pin "1") (pinfunction "1_1") (pintype "power_in"))
      (node (ref "C4") (pin "1") (pinfunction "1_1") (pintype "power_in"))
      (node (ref "C5") (pin "1") (pinfunction "1_1") (pintype "power_in"))
      (node (ref "C6") (pin "1") (pinfunction "1_1") (pintype "power_in"))
      (node (ref "C7") (pin "2") (pinfunction "2_2") (pintype "power_in"))
      (node (ref "L1") (pin "1") (pinfunction "1_1") (pintype "passive"))
      (node (ref "R7") (pin "2") (pinfunction "2_2") (pintype "passive"))
      (node (ref "X1") (pin "1") (pinfunction "1_1") (pintype "passive"))
    )
    (net (code "5") (name "/DIV24V") (class "Default")
      (node (ref "R11") (pin "1") (pinfunction "1_1") (pintype "passive"))
    )
    (net (code "6") (name "/HRPWM1") (class "Default")
      (node (ref "D1") (pin "1") (pinfunction "HIN_1") (pintype "input"))
      (node (ref "R5") (pin "2") (pinfunction "2_2") (pintype "passive"))
    )
    (net (code "7") (name "/HRPWM2") (class "Default")
      (node (ref "D1") (pin "2") (pinfunction "LIN_2") (pintype "input"))
      (node (ref "R6") (pin "2") (pinfunction "2_2") (pintype "passive"))
    )
    (net (code "8") (name "/I-INPUT") (class "Default")
      (node (ref "C17") (pin "2") (pinfunction "2_2") (pintype "power_in"))
      (node (ref "R26") (pin "1") (pinfunction "1_1") (pintype "passive"))
    )
    (net (code "9") (name "/I-OUTPUT") (class "Default")
      (node (ref "C15") (pin "2") (pinfunction "2_2") (pintype "power_in"))
      (node (ref "R20") (pin "2") (pinfunction "2_2") (pintype "passive"))
    )
    (net (code "10") (name "/V-INPUT") (class "Default")
      (node (ref "C13") (pin "2") (pinfunction "2_2") (pintype "power_in"))
      (node (ref "R13") (pin "1") (pinfunction "1_1") (pintype "passive"))
      (node (ref "R16") (pin "2") (pinfunction "2_2") (pintype "passive"))
    )
    (net (code "11") (name "/V-OUTPUT") (class "Default")
      (node (ref "C8") (pin "2") (pinfunction "2_2") (pintype "power_in"))
      (node (ref "R10") (pin "2") (pinfunction "2_2") (pintype "passive"))
      (node (ref "R7") (pin "1") (pinfunction "1_1") (pintype "passive"))
      (node (ref "R9") (pin "2") (pinfunction "2_2") (pintype "passive"))
    )
    (net (code "12") (name "GND") (class "Default")
      (node (ref "C10") (pin "2") (pinfunction "2_2") (pintype "power_in"))
      (node (ref "C11") (pin "2") (pinfunction "2_2") (pintype "power_in"))
      (node (ref "C12") (pin "2") (pinfunction "2_2") (pintype "power_in"))
      (node (ref "C13") (pin "1") (pinfunction "1_1") (pintype "power_in"))
      (node (ref "C15") (pin "1") (pinfunction "1_1") (pintype "power_in"))
      (node (ref "C17") (pin "1") (pinfunction "1_1") (pintype "power_in"))
      (node (ref "C2") (pin "1") (pinfunction "1_1") (pintype "power_in"))
      (node (ref "C20") (pin "1") (pinfunction "1_1") (pintype "power_in"))
      (node (ref "C21") (pin "1") (pinfunction "1_1") (pintype "power_in"))
      (node (ref "C22") (pin "1") (pinfunction "1_1") (pintype "power_in"))
      (node (ref "C23") (pin "1") (pinfunction "1_1") (pintype "power_in"))
      (node (ref "C24") (pin "1") (pinfunction "1_1") (pintype "power_in"))
      (node (ref "C25") (pin "1") (pinfunction "1_1") (pintype "power_in"))
      (node (ref "C26") (pin "1") (pinfunction "1_1") (pintype "power_in"))
      (node (ref "C27") (pin "1") (pinfunction "1_1") (pintype "power_in"))
      (node (ref "C28") (pin "1") (pinfunction "1_1") (pintype "power_in"))
      (node (ref "C29") (pin "1") (pinfunction "1_1") (pintype "power_in"))
      (node (ref "C3") (pin "2") (pinfunction "2_2") (pintype "power_in"))
      (node (ref "C4") (pin "2") (pinfunction "2_2") (pintype "power_in"))
      (node (ref "C5") (pin "2") (pinfunction "2_2") (pintype "power_in"))
      (node (ref "C6") (pin "2") (pinfunction "2_2") (pintype "power_in"))
      (node (ref "C7") (pin "1") (pinfunction "1_1") (pintype "power_in"))
      (node (ref "C8") (pin "1") (pinfunction "1_1") (pintype "power_in"))
      (node (ref "C9") (pin "2") (pinfunction "2_2") (pintype "power_in"))
      (node (ref "D1") (pin "3") (pinfunction "GND_3") (pintype "passive"))
      (node (ref "D2") (pin "2") (pinfunction "V-_2") (pintype "power_in"))
      (node (ref "D3") (pin "2") (pinfunction "V-_2") (pintype "power_in"))
      (node (ref "D4") (pin "2") (pinfunction "GND_2") (pintype "passive"))
      (node (ref "D5") (pin "0") (pinfunction "GND_0") (pintype "passive"))
      (node (ref "D5") (pin "1") (pinfunction "RTN_1") (pintype "passive"))
      (node (ref "R12") (pin "1") (pinfunction "1_1") (pintype "passive"))
      (node (ref "R15") (pin "2") (pinfunction "2_2") (pintype "passive"))
      (node (ref "R16") (pin "1") (pinfunction "1_1") (pintype "passive"))
      (node (ref "R19") (pin "2") (pinfunction "2_2") (pintype "passive"))
      (node (ref "R21") (pin "1") (pinfunction "1_1") (pintype "passive"))
      (node (ref "R25") (pin "1") (pinfunction "1_1") (pintype "passive"))
      (node (ref "R27") (pin "1") (pinfunction "1_1") (pintype "passive"))
      (node (ref "R28") (pin "2") (pinfunction "2_2") (pintype "passive"))
      (node (ref "R36") (pin "1") (pinfunction "1_1") (pintype "passive"))
      (node (ref "R38") (pin "1") (pinfunction "1_1") (pintype "passive"))
      (node (ref "R39") (pin "1") (pinfunction "1_1") (pintype "passive"))
      (node (ref "R5") (pin "1") (pinfunction "1_1") (pintype "passive"))
      (node (ref "R6") (pin "1") (pinfunction "1_1") (pintype "passive"))
      (node (ref "R8") (pin "1") (pinfunction "1_1") (pintype "passive"))
      (node (ref "R9") (pin "1") (pinfunction "1_1") (pintype "passive"))
      (node (ref "VD3") (pin "1") (pinfunction "1_1") (pintype "passive"))
      (node (ref "VT2") (pin "3") (pinfunction "S_3") (pintype "passive"))
      (node (ref "VT3") (pin "2") (pinfunction "S_2") (pintype "passive"))
    )
    (net (code "13") (name "Net-(C14-Pad1)") (class "Default")
      (node (ref "C14") (pin "1") (pinfunction "1_1") (pintype "power_in"))
      (node (ref "R24") (pin "1") (pinfunction "1_1") (pintype "passive"))
      (node (ref "R25") (pin "2") (pinfunction "2_2") (pintype "passive"))
    )
    (net (code "14") (name "Net-(C14-Pad2)") (class "Default")
      (node (ref "C14") (pin "2") (pinfunction "2_2") (pintype "power_in"))
      (node (ref "R17") (pin "1") (pinfunction "1_1") (pintype "passive"))
      (node (ref "R18") (pin "2") (pinfunction "2_2") (pintype "passive"))
    )
    (net (code "15") (name "Net-(C16-Pad1)") (class "Default")
      (node (ref "C16") (pin "1") (pinfunction "1_1") (pintype "power_in"))
      (node (ref "R28") (pin "1") (pinfunction "1_1") (pintype "passive"))
      (node (ref "R29") (pin "2") (pinfunction "2_2") (pintype "passive"))
    )
    (net (code "16") (name "Net-(C16-Pad2)") (class "Default")
      (node (ref "C16") (pin "2") (pinfunction "2_2") (pintype "power_in"))
      (node (ref "R22") (pin "1") (pinfunction "1_1") (pintype "passive"))
      (node (ref "R23") (pin "2") (pinfunction "2_2") (pintype "passive"))
    )
    (net (code "17") (name "Net-(D1-HO)") (class "Default")
      (node (ref "D1") (pin "7") (pinfunction "HO_7") (pintype "passive"))
      (node (ref "R2") (pin "2") (pinfunction "2_2") (pintype "passive"))
    )
    (net (code "18") (name "Net-(D1-LO)") (class "Default")
      (node (ref "D1") (pin "4") (pinfunction "LO_4") (pintype "passive"))
      (node (ref "R4") (pin "2") (pinfunction "2_2") (pintype "passive"))
    )
    (net (code "19") (name "Net-(D1-VB)") (class "Default")
      (node (ref "C1") (pin "2") (pinfunction "2_2") (pintype "power_in"))
      (node (ref "D1") (pin "8") (pinfunction "VB_8") (pintype "passive"))
      (node (ref "VD1") (pin "2") (pinfunction "2_2") (pintype "passive"))
    )
    (net (code "20") (name "Net-(D1-VS)") (class "Default")
      (node (ref "C1") (pin "1") (pinfunction "1_1") (pintype "power_in"))
      (node (ref "D1") (pin "6") (pinfunction "VS_6") (pintype "passive"))
      (node (ref "L1") (pin "2") (pinfunction "2_2") (pintype "passive"))
      (node (ref "R3") (pin "1") (pinfunction "1_1") (pintype "passive"))
      (node (ref "VT1") (pin "3") (pinfunction "S_3") (pintype "passive"))
      (node (ref "VT2") (pin "2") (pinfunction "D_2") (pintype "passive"))
    )
    (net (code "21") (name "Net-(D2-IN+)") (class "Default")
      (node (ref "D2") (pin "3") (pinfunction "IN+_3") (pintype "input"))
      (node (ref "R15") (pin "1") (pinfunction "1_1") (pintype "passive"))
      (node (ref "R17") (pin "2") (pinfunction "2_2") (pintype "passive"))
    )
    (net (code "22") (name "Net-(D2-IN-)") (class "Default")
      (node (ref "D2") (pin "4") (pinfunction "IN-_4") (pintype "input"))
      (node (ref "R24") (pin "2") (pinfunction "2_2") (pintype "passive"))
      (node (ref "R30") (pin "1") (pinfunction "1_1") (pintype "passive"))
    )
    (net (code "23") (name "Net-(D2-OUT)") (class "Default")
      (node (ref "D2") (pin "1") (pinfunction "OUT_1") (pintype "power_in"))
      (node (ref "R20") (pin "1") (pinfunction "1_1") (pintype "passive"))
      (node (ref "R30") (pin "2") (pinfunction "2_2") (pintype "passive"))
    )
    (net (code "24") (name "Net-(D3-IN+)") (class "Default")
      (node (ref "D3") (pin "3") (pinfunction "IN+_3") (pintype "input"))
      (node (ref "R19") (pin "1") (pinfunction "1_1") (pintype "passive"))
      (node (ref "R23") (pin "1") (pinfunction "1_1") (pintype "passive"))
    )
    (net (code "25") (name "Net-(D3-IN-)") (class "Default")
      (node (ref "D3") (pin "4") (pinfunction "IN-_4") (pintype "input"))
      (node (ref "R29") (pin "1") (pinfunction "1_1") (pintype "passive"))
      (node (ref "R31") (pin "2") (pinfunction "2_2") (pintype "passive"))
    )
    (net (code "26") (name "Net-(D3-OUT)") (class "Default")
      (node (ref "D3") (pin "1") (pinfunction "OUT_1") (pintype "power_in"))
      (node (ref "R26") (pin "2") (pinfunction "2_2") (pintype "passive"))
      (node (ref "R31") (pin "1") (pinfunction "1_1") (pintype "passive"))
    )
    (net (code "27") (name "Net-(D4-BS)") (class "Default")
      (node (ref "C18") (pin "2") (pinfunction "2_2") (pintype "power_in"))
      (node (ref "D4") (pin "1") (pinfunction "BS_1") (pintype "passive"))
    )
    (net (code "28") (name "Net-(D4-EN)") (class "Default")
      (node (ref "D4") (pin "4") (pinfunction "EN_4") (pintype "input"))
      (node (ref "R32") (pin "1") (pinfunction "1_1") (pintype "passive"))
    )
    (net (code "29") (name "Net-(D4-FB)") (class "Default")
      (node (ref "D4") (pin "3") (pinfunction "FB_3") (pintype "input"))
      (node (ref "R33") (pin "2") (pinfunction "2_2") (pintype "passive"))
      (node (ref "R36") (pin "2") (pinfunction "2_2") (pintype "passive"))
    )
    (net (code "30") (name "Net-(D4-SW)") (class "Default")
      (node (ref "C18") (pin "1") (pinfunction "1_1") (pintype "power_in"))
      (node (ref "D4") (pin "6") (pinfunction "SW_6") (pintype "passive"))
      (node (ref "L2") (pin "2") (pinfunction "2_2") (pintype "passive"))
      (node (ref "VD3") (pin "2") (pinfunction "2_2") (pintype "passive"))
    )
    (net (code "31") (name "Net-(D5-BST)") (class "Default")
      (node (ref "C19") (pin "2") (pinfunction "2_2") (pintype "power_in"))
      (node (ref "D5") (pin "7") (pinfunction "BST_7") (pintype "passive"))
    )
    (net (code "32") (name "Net-(D5-FB)") (class "Default")
      (node (ref "D5") (pin "5") (pinfunction "FB_5") (pintype "input"))
      (node (ref "R37") (pin "2") (pinfunction "2_2") (pintype "passive"))
      (node (ref "R39") (pin "2") (pinfunction "2_2") (pintype "passive"))
    )
    (net (code "33") (name "Net-(D5-RON)") (class "Default")
      (node (ref "D5") (pin "4") (pinfunction "RON_4") (pintype "input"))
      (node (ref "R34") (pin "1") (pinfunction "1_1") (pintype "passive"))
    )
    (net (code "34") (name "Net-(D5-SW)") (class "Default")
      (node (ref "C19") (pin "1") (pinfunction "1_1") (pintype "power_in"))
      (node (ref "D5") (pin "8") (pinfunction "SW_8") (pintype "passive"))
      (node (ref "L3") (pin "2") (pinfunction "2_2") (pintype "passive"))
    )
    (net (code "35") (name "Net-(D5-UVLO)") (class "Default")
      (node (ref "D5") (pin "3") (pinfunction "UVLO_3") (pintype "passive"))
      (node (ref "R35") (pin "1") (pinfunction "1_1") (pintype "passive"))
      (node (ref "R38") (pin "2") (pinfunction "2_2") (pintype "passive"))
    )
    (net (code "36") (name "Net-(D5-VCC)") (class "Default")
      (node (ref "C27") (pin "2") (pinfunction "2_2") (pintype "power_in"))
      (node (ref "D5") (pin "6") (pinfunction "VCC_6") (pintype "passive"))
      (node (ref "VD4") (pin "2") (pinfunction "2_2") (pintype "passive"))
    )
    (net (code "37") (name "Net-(R1-Pad1)") (class "Default")
      (node (ref "R1") (pin "1") (pinfunction "1_1") (pintype "passive"))
      (node (ref "VD1") (pin "1") (pinfunction "1_1") (pintype "passive"))
    )
    (net (code "38") (name "Net-(R18-Pad1)") (class "Default")
      (node (ref "R18") (pin "1") (pinfunction "1_1") (pintype "passive"))
      (node (ref "R21") (pin "2") (pinfunction "2_2") (pintype "passive"))
      (node (ref "X1") (pin "2") (pinfunction "2_2") (pintype "passive"))
    )
    (net (code "39") (name "Net-(VD2-A)") (class "Default")
      (node (ref "R22") (pin "2") (pinfunction "2_2") (pintype "passive"))
      (node (ref "R27") (pin "2") (pinfunction "2_2") (pintype "passive"))
      (node (ref "VD2") (pin "1") (pinfunction "A_1") (pintype "passive"))
      (node (ref "VT4") (pin "3") (pinfunction "S_3") (pintype "passive"))
    )
    (net (code "40") (name "Net-(VD2-C)") (class "Default")
      (node (ref "R14") (pin "1") (pinfunction "1_1") (pintype "passive"))
      (node (ref "VD2") (pin "2") (pinfunction "C_2") (pintype "passive"))
      (node (ref "VT4") (pin "1") (pinfunction "G_1") (pintype "passive"))
    )
    (net (code "41") (name "Net-(VT1-G)") (class "Default")
      (node (ref "R2") (pin "1") (pinfunction "1_1") (pintype "passive"))
      (node (ref "R3") (pin "2") (pinfunction "2_2") (pintype "passive"))
      (node (ref "VT1") (pin "1") (pinfunction "G_1") (pintype "passive"))
    )
    (net (code "42") (name "Net-(VT2-G)") (class "Default")
      (node (ref "R4") (pin "1") (pinfunction "1_1") (pintype "passive"))
      (node (ref "R8") (pin "2") (pinfunction "2_2") (pintype "passive"))
      (node (ref "VT2") (pin "1") (pinfunction "G_1") (pintype "passive"))
    )
    (net (code "43") (name "Net-(VT3-D)") (class "Default")
      (node (ref "R10") (pin "1") (pinfunction "1_1") (pintype "passive"))
      (node (ref "VT3") (pin "3") (pinfunction "D_3") (pintype "passive"))
    )
    (net (code "44") (name "Net-(VT3-G)") (class "Default")
      (node (ref "R11") (pin "2") (pinfunction "2_2") (pintype "passive"))
      (node (ref "R12") (pin "2") (pinfunction "2_2") (pintype "passive"))
      (node (ref "VT3") (pin "1") (pinfunction "G_1") (pintype "passive"))
    )
    (net (code "45") (name "Net-(VT4-D)") (class "Default")
      (node (ref "VT4") (pin "2") (pinfunction "D_2") (pintype "passive"))
      (node (ref "X2") (pin "2") (pinfunction "2_2") (pintype "passive"))
    )
    (net (code "46") (name "VCC12V") (class "Default")
      (node (ref "C20") (pin "2") (pinfunction "2_2") (pintype "power_in"))
      (node (ref "C28") (pin "2") (pinfunction "2_2") (pintype "power_in"))
      (node (ref "C29") (pin "2") (pinfunction "2_2") (pintype "power_in"))
      (node (ref "D4") (pin "5") (pinfunction "VIN_5") (pintype "passive"))
      (node (ref "L3") (pin "1") (pinfunction "1_1") (pintype "passive"))
      (node (ref "R32") (pin "2") (pinfunction "2_2") (pintype "passive"))
      (node (ref "R37") (pin "1") (pinfunction "1_1") (pintype "passive"))
      (node (ref "VD4") (pin "1") (pinfunction "1_1") (pintype "passive"))
    )
    (net (code "47") (name "VIN") (class "Default")
      (node (ref "C25") (pin "2") (pinfunction "2_2") (pintype "power_in"))
      (node (ref "C26") (pin "2") (pinfunction "2_2") (pintype "power_in"))
      (node (ref "D5") (pin "2") (pinfunction "VIN_2") (pintype "passive"))
      (node (ref "R34") (pin "2") (pinfunction "2_2") (pintype "passive"))
      (node (ref "R35") (pin "2") (pinfunction "2_2") (pintype "passive"))
    )
  )
)
